# Peripherals.net
KiCad netlist of a schematic drawn in Altium Designer
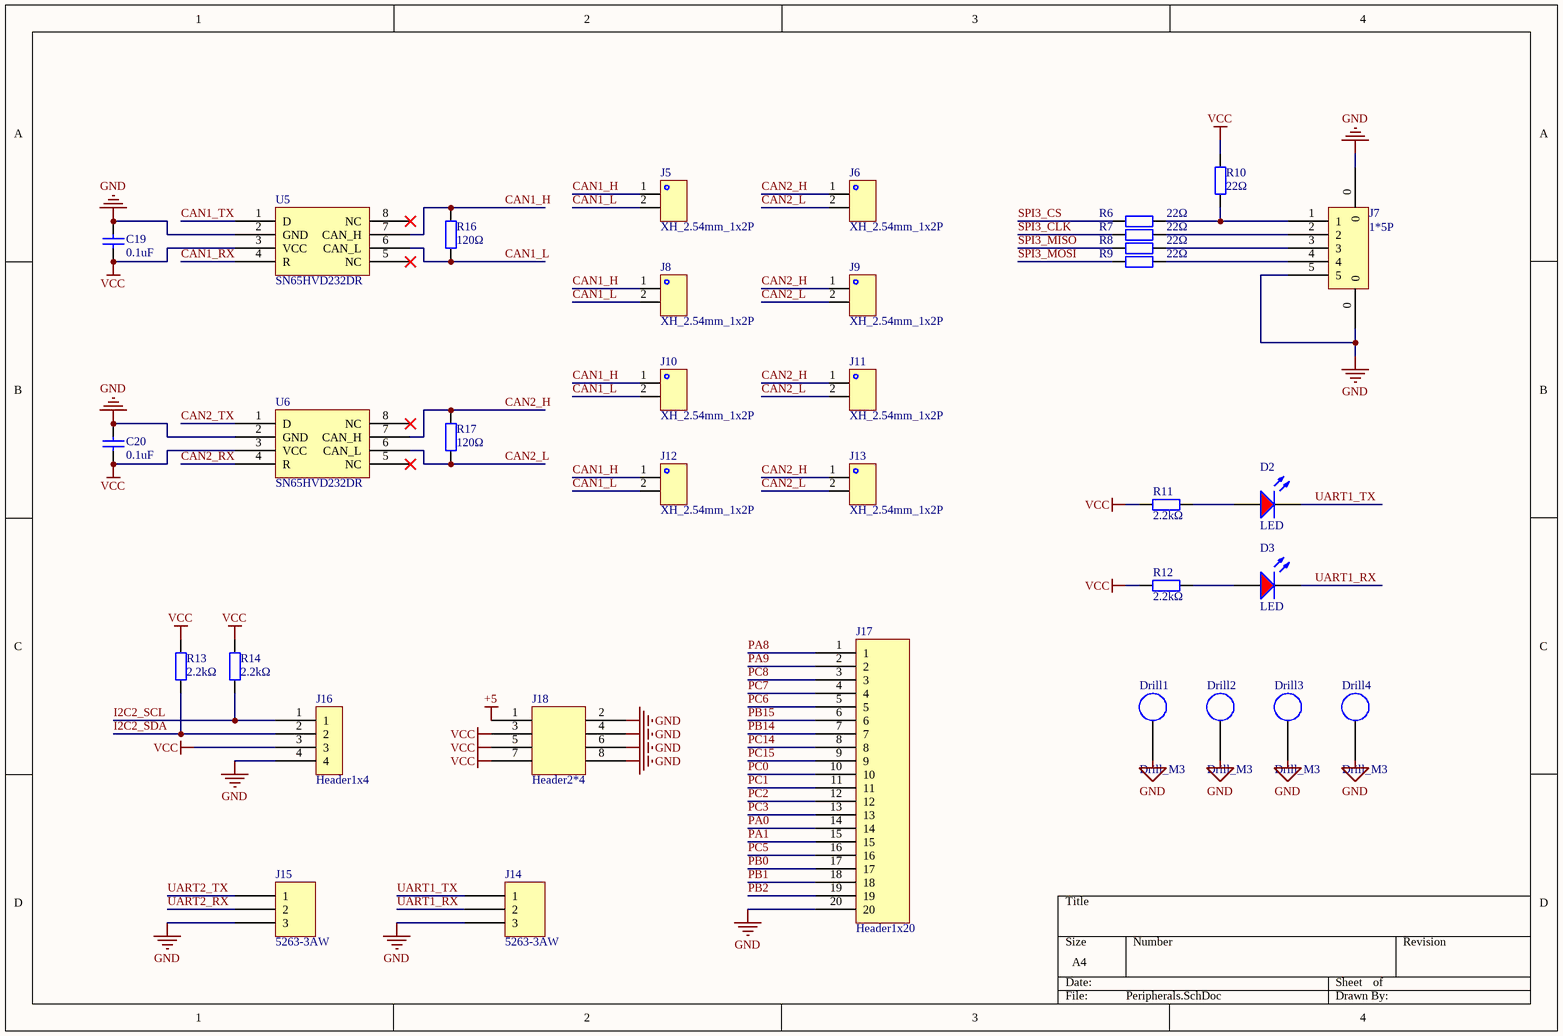
[diagram p0: Peripherals.SchDoc]

(export (version "E")
  (design (tool "Eeschema 10.0.6"))
  (components
    (comp (ref "C19") (value "0.1uF") (footprint "C0603") (libsource (lib "NetTie") (part "Capacitor")))
    (comp (ref "C20") (value "0.1uF") (footprint "C0603") (libsource (lib "NetTie") (part "Capacitor")))
    (comp (ref "D2")
      (value "LED")
      (footprint "0603_LED_S1")
      (description "发光二极管")
      (libsource (lib "LED") (part "0603 红灯"))
    )
    (comp (ref "D3")
      (value "LED")
      (footprint "0603_LED_S1")
      (description "发光二极管")
      (libsource (lib "LED") (part "0603 红灯"))
    )
    (comp (ref "Drill1")
      (value "Drill_M3")
      (footprint "Drill_M_3")
      (libsource (lib "NetTie") (part "Drill_M3"))
    )
    (comp (ref "Drill2")
      (value "Drill_M3")
      (footprint "Drill_M_3")
      (libsource (lib "NetTie") (part "Drill_M3"))
    )
    (comp (ref "Drill3")
      (value "Drill_M3")
      (footprint "Drill_M_3")
      (libsource (lib "NetTie") (part "Drill_M3"))
    )
    (comp (ref "Drill4")
      (value "Drill_M3")
      (footprint "Drill_M_3")
      (libsource (lib "NetTie") (part "Drill_M3"))
    )
    (comp (ref "J5")
      (value "XH_2.54mm_1x2P")
      (footprint "XH2.54mm1x2P弯插")
      (libsource (lib "Connectors") (part "XH_2.54mm_1x2P"))
    )
    (comp (ref "J6")
      (value "XH_2.54mm_1x2P")
      (footprint "XH2.54mm1x2P弯插")
      (libsource (lib "Connectors") (part "XH_2.54mm_1x2P"))
    )
    (comp (ref "J7")
      (value "1*5P")
      (footprint "1.0T-5P")
      (description "C145957")
      (libsource (lib "Connectors") (part "插座 1*5P 卧贴"))
    )
    (comp (ref "J8")
      (value "XH_2.54mm_1x2P")
      (footprint "XH2.54mm1x2P弯插")
      (libsource (lib "Connectors") (part "XH_2.54mm_1x2P"))
    )
    (comp (ref "J9")
      (value "XH_2.54mm_1x2P")
      (footprint "XH2.54mm1x2P弯插")
      (libsource (lib "Connectors") (part "XH_2.54mm_1x2P"))
    )
    (comp (ref "J10")
      (value "XH_2.54mm_1x2P")
      (footprint "XH2.54mm1x2P弯插")
      (libsource (lib "Connectors") (part "XH_2.54mm_1x2P"))
    )
    (comp (ref "J11")
      (value "XH_2.54mm_1x2P")
      (footprint "XH2.54mm1x2P弯插")
      (libsource (lib "Connectors") (part "XH_2.54mm_1x2P"))
    )
    (comp (ref "J12")
      (value "XH_2.54mm_1x2P")
      (footprint "XH2.54mm1x2P弯插")
      (libsource (lib "Connectors") (part "XH_2.54mm_1x2P"))
    )
    (comp (ref "J13")
      (value "XH_2.54mm_1x2P")
      (footprint "XH2.54mm1x2P弯插")
      (libsource (lib "Connectors") (part "XH_2.54mm_1x2P"))
    )
    (comp (ref "J14")
      (value "5263-3AW")
      (footprint "5264-3AW")
      (libsource (lib "Connectors") (part "5263-3AW"))
    )
    (comp (ref "J15")
      (value "5263-3AW")
      (footprint "5264-3AW")
      (libsource (lib "Connectors") (part "5263-3AW"))
    )
    (comp (ref "J16")
      (value "Header1x4")
      (footprint "Header 1x4p")
      (libsource (lib "Connectors") (part "Header1x4"))
    )
    (comp (ref "J17")
      (value "Header1x20")
      (footprint "Header1x20")
      (libsource (lib "Connectors") (part "Header1x20"))
    )
    (comp (ref "J18")
      (value "Header2*4")
      (footprint "Header2*4")
      (description "C124386")
      (libsource (lib "Connectors") (part "Header2*4"))
    )
    (comp (ref "R6") (value "22Ω") (footprint "R0603") (libsource (lib "") (part "Resistor_1")))
    (comp (ref "R7") (value "22Ω") (footprint "R0603") (libsource (lib "") (part "Resistor_1")))
    (comp (ref "R8") (value "22Ω") (footprint "R0603") (libsource (lib "") (part "Resistor_1")))
    (comp (ref "R9") (value "22Ω") (footprint "R0603") (libsource (lib "") (part "Resistor_1")))
    (comp (ref "R10") (value "22Ω") (footprint "R0603") (libsource (lib "NetTie") (part "Resistor")))
    (comp (ref "R11") (value "2.2kΩ") (footprint "R0603") (libsource (lib "") (part "Resistor_3")))
    (comp (ref "R12") (value "2.2kΩ") (footprint "R0603") (libsource (lib "") (part "Resistor_3")))
    (comp (ref "R13") (value "2.2kΩ") (footprint "R0603") (libsource (lib "NetTie") (part "Resistor")))
    (comp (ref "R14") (value "2.2kΩ") (footprint "R0603") (libsource (lib "NetTie") (part "Resistor")))
    (comp (ref "R16") (value "120Ω") (footprint "R0603") (libsource (lib "") (part "Resistor_2")))
    (comp (ref "R17") (value "120Ω") (footprint "R0603") (libsource (lib "") (part "Resistor_2")))
    (comp (ref "U5")
      (value "SN65HVD232DR")
      (footprint "SOIC-8_150mil")
      (description "C30530")
      (libsource (lib "NetTie") (part "SN65HVD232DR"))
    )
    (comp (ref "U6")
      (value "SN65HVD232DR")
      (footprint "SOIC-8_150mil")
      (description "C30530")
      (libsource (lib "NetTie") (part "SN65HVD232DR"))
    )
  )
  (nets
    (net (code "1") (name "+5") (class "Default")
      (node (ref "J18") (pin "1") (pinfunction "A_1") (pintype "passive"))
    )
    (net (code "2") (name "/CAN1_H") (class "Default")
      (node (ref "J10") (pin "1") (pinfunction "1_1") (pintype "passive"))
      (node (ref "J12") (pin "1") (pinfunction "1_1") (pintype "passive"))
      (node (ref "J5") (pin "1") (pinfunction "1_1") (pintype "passive"))
      (node (ref "J8") (pin "1") (pinfunction "1_1") (pintype "passive"))
      (node (ref "R16") (pin "1") (pinfunction "1_1") (pintype "passive"))
      (node (ref "U5") (pin "7") (pinfunction "CAN_H_7") (pintype "passive"))
    )
    (net (code "3") (name "/CAN1_L") (class "Default")
      (node (ref "J10") (pin "2") (pinfunction "2_2") (pintype "passive"))
      (node (ref "J12") (pin "2") (pinfunction "2_2") (pintype "passive"))
      (node (ref "J5") (pin "2") (pinfunction "2_2") (pintype "passive"))
      (node (ref "J8") (pin "2") (pinfunction "2_2") (pintype "passive"))
      (node (ref "R16") (pin "2") (pinfunction "2_2") (pintype "passive"))
      (node (ref "U5") (pin "6") (pinfunction "CAN_L_6") (pintype "passive"))
    )
    (net (code "4") (name "/CAN1_RX") (class "Default")
      (node (ref "U5") (pin "4") (pinfunction "R_4") (pintype "passive"))
    )
    (net (code "5") (name "/CAN1_TX") (class "Default")
      (node (ref "U5") (pin "1") (pinfunction "D_1") (pintype "passive"))
    )
    (net (code "6") (name "/CAN2_H") (class "Default")
      (node (ref "J11") (pin "1") (pinfunction "1_1") (pintype "passive"))
      (node (ref "J13") (pin "1") (pinfunction "1_1") (pintype "passive"))
      (node (ref "J6") (pin "1") (pinfunction "1_1") (pintype "passive"))
      (node (ref "J9") (pin "1") (pinfunction "1_1") (pintype "passive"))
      (node (ref "R17") (pin "1") (pinfunction "1_1") (pintype "passive"))
      (node (ref "U6") (pin "7") (pinfunction "CAN_H_7") (pintype "passive"))
    )
    (net (code "7") (name "/CAN2_L") (class "Default")
      (node (ref "J11") (pin "2") (pinfunction "2_2") (pintype "passive"))
      (node (ref "J13") (pin "2") (pinfunction "2_2") (pintype "passive"))
      (node (ref "J6") (pin "2") (pinfunction "2_2") (pintype "passive"))
      (node (ref "J9") (pin "2") (pinfunction "2_2") (pintype "passive"))
      (node (ref "R17") (pin "2") (pinfunction "2_2") (pintype "passive"))
      (node (ref "U6") (pin "6") (pinfunction "CAN_L_6") (pintype "passive"))
    )
    (net (code "8") (name "/CAN2_RX") (class "Default")
      (node (ref "U6") (pin "4") (pinfunction "R_4") (pintype "passive"))
    )
    (net (code "9") (name "/CAN2_TX") (class "Default")
      (node (ref "U6") (pin "1") (pinfunction "D_1") (pintype "passive"))
    )
    (net (code "10") (name "/I2C2_SCL") (class "Default")
      (node (ref "J16") (pin "1") (pinfunction "1_1") (pintype "passive"))
      (node (ref "R14") (pin "1") (pinfunction "1_1") (pintype "passive"))
    )
    (net (code "11") (name "/I2C2_SDA") (class "Default")
      (node (ref "J16") (pin "2") (pinfunction "2_2") (pintype "passive"))
      (node (ref "R13") (pin "1") (pinfunction "1_1") (pintype "passive"))
    )
    (net (code "12") (name "/PA0") (class "Default")
      (node (ref "J17") (pin "14") (pinfunction "14_14") (pintype "passive"))
    )
    (net (code "13") (name "/PA1") (class "Default")
      (node (ref "J17") (pin "15") (pinfunction "15_15") (pintype "passive"))
    )
    (net (code "14") (name "/PA8") (class "Default")
      (node (ref "J17") (pin "1") (pinfunction "1_1") (pintype "passive"))
    )
    (net (code "15") (name "/PA9") (class "Default")
      (node (ref "J17") (pin "2") (pinfunction "2_2") (pintype "passive"))
    )
    (net (code "16") (name "/PB0") (class "Default")
      (node (ref "J17") (pin "17") (pinfunction "17_17") (pintype "passive"))
    )
    (net (code "17") (name "/PB1") (class "Default")
      (node (ref "J17") (pin "18") (pinfunction "18_18") (pintype "passive"))
    )
    (net (code "18") (name "/PB2") (class "Default")
      (node (ref "J17") (pin "19") (pinfunction "19_19") (pintype "passive"))
    )
    (net (code "19") (name "/PB14") (class "Default")
      (node (ref "J17") (pin "7") (pinfunction "7_7") (pintype "passive"))
    )
    (net (code "20") (name "/PB15") (class "Default")
      (node (ref "J17") (pin "6") (pinfunction "6_6") (pintype "passive"))
    )
    (net (code "21") (name "/PC0") (class "Default")
      (node (ref "J17") (pin "10") (pinfunction "10_10") (pintype "passive"))
    )
    (net (code "22") (name "/PC1") (class "Default")
      (node (ref "J17") (pin "11") (pinfunction "11_11") (pintype "passive"))
    )
    (net (code "23") (name "/PC2") (class "Default")
      (node (ref "J17") (pin "12") (pinfunction "12_12") (pintype "passive"))
    )
    (net (code "24") (name "/PC3") (class "Default")
      (node (ref "J17") (pin "13") (pinfunction "13_13") (pintype "passive"))
    )
    (net (code "25") (name "/PC5") (class "Default")
      (node (ref "J17") (pin "16") (pinfunction "16_16") (pintype "passive"))
    )
    (net (code "26") (name "/PC6") (class "Default")
      (node (ref "J17") (pin "5") (pinfunction "5_5") (pintype "passive"))
    )
    (net (code "27") (name "/PC7") (class "Default")
      (node (ref "J17") (pin "4") (pinfunction "4_4") (pintype "passive"))
    )
    (net (code "28") (name "/PC8") (class "Default")
      (node (ref "J17") (pin "3") (pinfunction "3_3") (pintype "passive"))
    )
    (net (code "29") (name "/PC14") (class "Default")
      (node (ref "J17") (pin "8") (pinfunction "8_8") (pintype "passive"))
    )
    (net (code "30") (name "/PC15") (class "Default")
      (node (ref "J17") (pin "9") (pinfunction "9_9") (pintype "passive"))
    )
    (net (code "31") (name "/SPI3_CLK") (class "Default")
      (node (ref "R7") (pin "2") (pinfunction "2_2") (pintype "passive"))
    )
    (net (code "32") (name "/SPI3_CS") (class "Default")
      (node (ref "R6") (pin "2") (pinfunction "2_2") (pintype "passive"))
    )
    (net (code "33") (name "/SPI3_MISO") (class "Default")
      (node (ref "R8") (pin "2") (pinfunction "2_2") (pintype "passive"))
    )
    (net (code "34") (name "/SPI3_MOSI") (class "Default")
      (node (ref "R9") (pin "2") (pinfunction "2_2") (pintype "passive"))
    )
    (net (code "35") (name "/UART1_RX") (class "Default")
      (node (ref "D3") (pin "K") (pinfunction "K_K") (pintype "passive"))
      (node (ref "J14") (pin "2") (pinfunction "2_2") (pintype "passive"))
    )
    (net (code "36") (name "/UART1_TX") (class "Default")
      (node (ref "D2") (pin "K") (pinfunction "K_K") (pintype "passive"))
      (node (ref "J14") (pin "1") (pinfunction "1_1") (pintype "passive"))
    )
    (net (code "37") (name "/UART2_RX") (class "Default")
      (node (ref "J15") (pin "2") (pinfunction "2_2") (pintype "passive"))
    )
    (net (code "38") (name "/UART2_TX") (class "Default")
      (node (ref "J15") (pin "1") (pinfunction "1_1") (pintype "passive"))
    )
    (net (code "39") (name "GND") (class "Default")
      (node (ref "C19") (pin "2") (pinfunction "2_2") (pintype "passive"))
      (node (ref "C20") (pin "2") (pinfunction "2_2") (pintype "passive"))
      (node (ref "Drill1") (pin "0") (pinfunction "A_0") (pintype "passive"))
      (node (ref "Drill2") (pin "0") (pinfunction "A_0") (pintype "passive"))
      (node (ref "Drill3") (pin "0") (pinfunction "A_0") (pintype "passive"))
      (node (ref "Drill4") (pin "0") (pinfunction "A_0") (pintype "passive"))
      (node (ref "J14") (pin "3") (pinfunction "3_3") (pintype "passive"))
      (node (ref "J15") (pin "3") (pinfunction "3_3") (pintype "passive"))
      (node (ref "J16") (pin "4") (pinfunction "4_4") (pintype "passive"))
      (node (ref "J17") (pin "20") (pinfunction "20_20") (pintype "passive"))
      (node (ref "J18") (pin "2") (pinfunction "A_2") (pintype "passive"))
      (node (ref "J18") (pin "4") (pinfunction "A_4") (pintype "passive"))
      (node (ref "J18") (pin "6") (pinfunction "A_6") (pintype "passive"))
      (node (ref "J18") (pin "8") (pinfunction "A_8") (pintype "passive"))
      (node (ref "J7") (pin "0") (pinfunction "0_0") (pintype "passive"))
      (node (ref "J7") (pin "5") (pinfunction "5_5") (pintype "passive"))
      (node (ref "U5") (pin "2") (pinfunction "GND_2") (pintype "passive"))
      (node (ref "U6") (pin "2") (pinfunction "GND_2") (pintype "passive"))
    )
    (net (code "40") (name "Net-(D2-PadA)") (class "Default")
      (node (ref "D2") (pin "A") (pinfunction "A_A") (pintype "passive"))
      (node (ref "R11") (pin "2") (pinfunction "2_2") (pintype "passive"))
    )
    (net (code "41") (name "Net-(D3-PadA)") (class "Default")
      (node (ref "D3") (pin "A") (pinfunction "A_A") (pintype "passive"))
      (node (ref "R12") (pin "2") (pinfunction "2_2") (pintype "passive"))
    )
    (net (code "42") (name "Net-(J7-Pad1)") (class "Default")
      (node (ref "J7") (pin "1") (pinfunction "1_1") (pintype "passive"))
      (node (ref "R10") (pin "1") (pinfunction "1_1") (pintype "passive"))
      (node (ref "R6") (pin "1") (pinfunction "1_1") (pintype "passive"))
    )
    (net (code "43") (name "Net-(J7-Pad2)") (class "Default")
      (node (ref "J7") (pin "2") (pinfunction "2_2") (pintype "passive"))
      (node (ref "R7") (pin "1") (pinfunction "1_1") (pintype "passive"))
    )
    (net (code "44") (name "Net-(J7-Pad3)") (class "Default")
      (node (ref "J7") (pin "3") (pinfunction "3_3") (pintype "passive"))
      (node (ref "R8") (pin "1") (pinfunction "1_1") (pintype "passive"))
    )
    (net (code "45") (name "Net-(J7-Pad4)") (class "Default")
      (node (ref "J7") (pin "4") (pinfunction "4_4") (pintype "passive"))
      (node (ref "R9") (pin "1") (pinfunction "1_1") (pintype "passive"))
    )
    (net (code "46") (name "VCC") (class "Default")
      (node (ref "C19") (pin "1") (pinfunction "1_1") (pintype "passive"))
      (node (ref "C20") (pin "1") (pinfunction "1_1") (pintype "passive"))
      (node (ref "J16") (pin "3") (pinfunction "3_3") (pintype "passive"))
      (node (ref "J18") (pin "3") (pinfunction "A_3") (pintype "passive"))
      (node (ref "J18") (pin "5") (pinfunction "A_5") (pintype "passive"))
      (node (ref "J18") (pin "7") (pinfunction "A_7") (pintype "passive"))
      (node (ref "R10") (pin "2") (pinfunction "2_2") (pintype "passive"))
      (node (ref "R11") (pin "1") (pinfunction "1_1") (pintype "passive"))
      (node (ref "R12") (pin "1") (pinfunction "1_1") (pintype "passive"))
      (node (ref "R13") (pin "2") (pinfunction "2_2") (pintype "passive"))
      (node (ref "R14") (pin "2") (pinfunction "2_2") (pintype "passive"))
      (node (ref "U5") (pin "3") (pinfunction "VCC_3") (pintype "passive"))
      (node (ref "U6") (pin "3") (pinfunction "VCC_3") (pintype "passive"))
    )
    (net (code "47") (name "unconnected-(U5-NC-Pad5)") (class "Default")
      (node (ref "U5") (pin "5") (pinfunction "NC_5") (pintype "passive+no_connect"))
    )
    (net (code "48") (name "unconnected-(U5-NC-Pad8)") (class "Default")
      (node (ref "U5") (pin "8") (pinfunction "NC_8") (pintype "passive+no_connect"))
    )
    (net (code "49") (name "unconnected-(U6-NC-Pad5)") (class "Default")
      (node (ref "U6") (pin "5") (pinfunction "NC_5") (pintype "passive+no_connect"))
    )
    (net (code "50") (name "unconnected-(U6-NC-Pad8)") (class "Default")
      (node (ref "U6") (pin "8") (pinfunction "NC_8") (pintype "passive+no_connect"))
    )
  )
)
